# MCU.net
KiCad netlist of a schematic drawn in Altium Designer
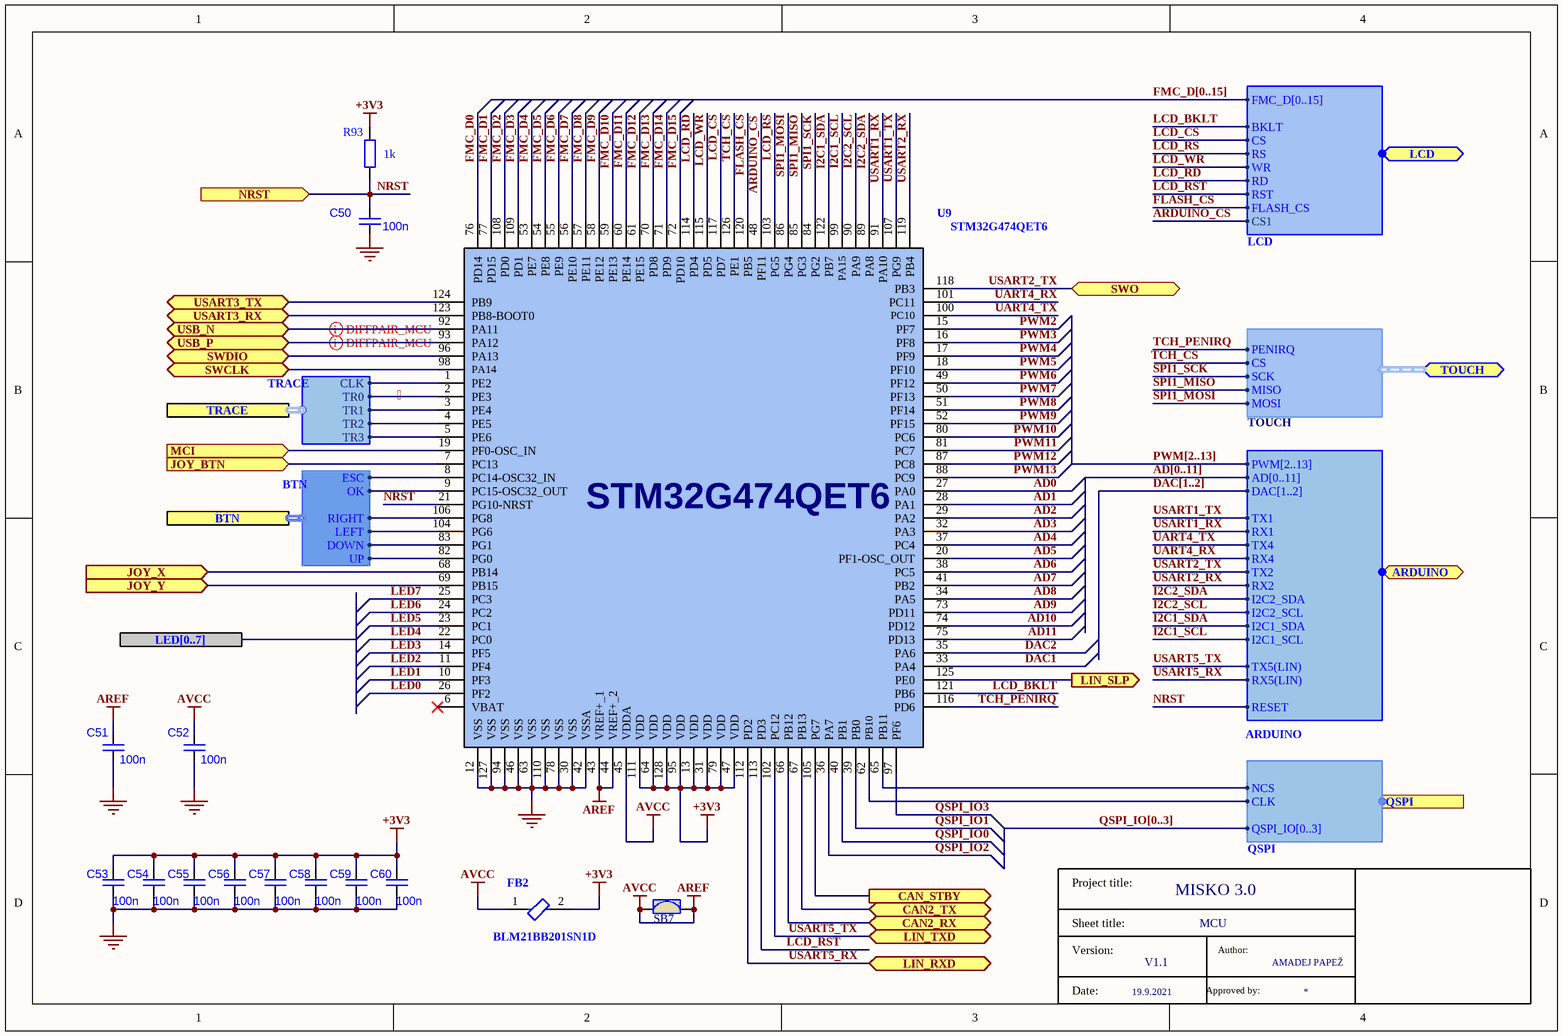
[diagram p0: MCU.SchDoc]

(export (version "E")
  (design (tool "Eeschema 10.0.6"))
  (components
    (comp (ref "C50")
      (value "100n")
      (footprint "C0603")
      (description "Capacitor")
      (libsource (lib "MISKO3_V6") (part "C"))
    )
    (comp (ref "C51")
      (value "100n")
      (footprint "C0603")
      (description "Capacitor")
      (libsource (lib "MISKO3_V6") (part "C"))
    )
    (comp (ref "C52")
      (value "100n")
      (footprint "C0603")
      (description "Capacitor")
      (libsource (lib "MISKO3_V6") (part "C"))
    )
    (comp (ref "C53")
      (value "100n")
      (footprint "C0603")
      (description "Capacitor")
      (libsource (lib "MISKO3_V6") (part "C"))
    )
    (comp (ref "C54")
      (value "100n")
      (footprint "C0603")
      (description "Capacitor")
      (libsource (lib "MISKO3_V6") (part "C"))
    )
    (comp (ref "C55")
      (value "100n")
      (footprint "C0603")
      (description "Capacitor")
      (libsource (lib "MISKO3_V6") (part "C"))
    )
    (comp (ref "C56")
      (value "100n")
      (footprint "C0603")
      (description "Capacitor")
      (libsource (lib "MISKO3_V6") (part "C"))
    )
    (comp (ref "C57")
      (value "100n")
      (footprint "C0603")
      (description "Capacitor")
      (libsource (lib "MISKO3_V6") (part "C"))
    )
    (comp (ref "C58")
      (value "100n")
      (footprint "C0603")
      (description "Capacitor")
      (libsource (lib "MISKO3_V6") (part "C"))
    )
    (comp (ref "C59")
      (value "100n")
      (footprint "C0603")
      (description "Capacitor")
      (libsource (lib "MISKO3_V6") (part "C"))
    )
    (comp (ref "C60")
      (value "100n")
      (footprint "C0603")
      (description "Capacitor")
      (libsource (lib "MISKO3_V6") (part "C"))
    )
    (comp (ref "FB2")
      (value "BLM21BB201SN1D")
      (footprint "BLM2102FB0805")
      (description "Chip Ferrite Bead, 0805, 200Ω @ 100MHz, 0.26Ω, 25%, 500mA")
      (fields (field (name "TOLERANCE") "25%"))
      (libsource (lib "MISKO3_V6") (part "BLM21BB201SN1D"))
    )
    (comp (ref "R93")
      (value "1k")
      (footprint "R1608_0603I_L")
      (description "R")
      (libsource (lib "MISKO3_V6") (part "R"))
    )
    (comp (ref "SB7")
      (value "SD_JUMP")
      (footprint "SOLDER_JUMPER")
      (libsource (lib "MISKO3_V6") (part "SD_JUMP"))
    )
    (comp (ref "T11") (value "~") (libsource (lib "MISKO3_V6") (part "Title block")))
    (comp (ref "U9")
      (value "STM32G474QET6")
      (footprint "QFP40P1600X1600X160-128N")
      (fields (field (name "MOUSER PART NUMBER") "511-STM32G474QET6"))
      (libsource (lib "MISKO3_V6") (part "STM32G474QET6"))
    )
  )
  (nets
    (net (code "7") (name "+3V3") (class "Default")
      (node (ref "C53") (pin "2") (pinfunction "2_2") (pintype "passive"))
      (node (ref "C54") (pin "2") (pinfunction "2_2") (pintype "passive"))
      (node (ref "C55") (pin "2") (pinfunction "2_2") (pintype "passive"))
      (node (ref "C56") (pin "2") (pinfunction "2_2") (pintype "passive"))
      (node (ref "C57") (pin "2") (pinfunction "2_2") (pintype "passive"))
      (node (ref "C58") (pin "2") (pinfunction "2_2") (pintype "passive"))
      (node (ref "C59") (pin "2") (pinfunction "2_2") (pintype "passive"))
      (node (ref "C60") (pin "2") (pinfunction "2_2") (pintype "passive"))
      (node (ref "FB2") (pin "2") (pinfunction "2_2") (pintype "passive"))
      (node (ref "R93") (pin "1") (pintype "passive"))
      (node (ref "U9") (pin "111") (pinfunction "VDD_111") (pintype "passive"))
      (node (ref "U9") (pin "128") (pinfunction "VDD_128") (pintype "passive"))
      (node (ref "U9") (pin "13") (pinfunction "VDD_13") (pintype "passive"))
      (node (ref "U9") (pin "31") (pinfunction "VDD_31") (pintype "passive"))
      (node (ref "U9") (pin "47") (pinfunction "VDD_47") (pintype "passive"))
      (node (ref "U9") (pin "64") (pinfunction "VDD_64") (pintype "passive"))
      (node (ref "U9") (pin "79") (pinfunction "VDD_79") (pintype "passive"))
      (node (ref "U9") (pin "95") (pinfunction "VDD_95") (pintype "passive"))
    )
    (net (code "9") (name "/AD0") (class "Default")
      (node (ref "U9") (pin "27") (pinfunction "PA0_27") (pintype "passive"))
    )
    (net (code "10") (name "/AD1") (class "Default")
      (node (ref "U9") (pin "28") (pinfunction "PA1_28") (pintype "passive"))
    )
    (net (code "11") (name "/AD2") (class "Default")
      (node (ref "U9") (pin "29") (pinfunction "PA2_29") (pintype "passive"))
    )
    (net (code "12") (name "/AD3") (class "Default")
      (node (ref "U9") (pin "32") (pinfunction "PA3_32") (pintype "passive"))
    )
    (net (code "13") (name "/AD4") (class "Default")
      (node (ref "U9") (pin "37") (pinfunction "PC4_37") (pintype "passive"))
    )
    (net (code "14") (name "/AD5") (class "Default")
      (node (ref "U9") (pin "20") (pinfunction "PF1-OSC_OUT_20") (pintype "passive"))
    )
    (net (code "15") (name "/AD6") (class "Default")
      (node (ref "U9") (pin "38") (pinfunction "PC5_38") (pintype "passive"))
    )
    (net (code "16") (name "/AD7") (class "Default")
      (node (ref "U9") (pin "41") (pinfunction "PB2_41") (pintype "passive"))
    )
    (net (code "17") (name "/AD8") (class "Default")
      (node (ref "U9") (pin "34") (pinfunction "PA5_34") (pintype "passive"))
    )
    (net (code "18") (name "/AD9") (class "Default")
      (node (ref "U9") (pin "73") (pinfunction "PD11_73") (pintype "passive"))
    )
    (net (code "19") (name "/AD10") (class "Default")
      (node (ref "U9") (pin "74") (pinfunction "PD12_74") (pintype "passive"))
    )
    (net (code "20") (name "/AD11") (class "Default")
      (node (ref "U9") (pin "75") (pinfunction "PD13_75") (pintype "passive"))
    )
    (net (code "22") (name "/ARDUINO_CS") (class "Default")
      (node (ref "U9") (pin "48") (pinfunction "PF11_48") (pintype "passive"))
    )
    (net (code "24") (name "/CAN2_RX") (class "Default")
      (node (ref "U9") (pin "66") (pinfunction "PB12_66") (pintype "passive"))
    )
    (net (code "25") (name "/CAN2_TX") (class "Default")
      (node (ref "U9") (pin "67") (pinfunction "PB13_67") (pintype "passive"))
    )
    (net (code "26") (name "/CAN_STBY") (class "Default")
      (node (ref "U9") (pin "105") (pinfunction "PG7_105") (pintype "passive"))
    )
    (net (code "27") (name "/DAC1") (class "Default")
      (node (ref "U9") (pin "33") (pinfunction "PA4_33") (pintype "passive"))
    )
    (net (code "28") (name "/DAC2") (class "Default")
      (node (ref "U9") (pin "35") (pinfunction "PA6_35") (pintype "passive"))
    )
    (net (code "29") (name "/DOWN") (class "Default")
      (node (ref "U9") (pin "83") (pinfunction "PG1_83") (pintype "passive"))
    )
    (net (code "30") (name "/ESC") (class "Default")
      (node (ref "U9") (pin "8") (pinfunction "PC14-OSC32_IN_8") (pintype "passive"))
    )
    (net (code "31") (name "/FLASH_CS") (class "Default")
      (node (ref "U9") (pin "120") (pinfunction "PB5_120") (pintype "passive"))
    )
    (net (code "32") (name "/FMC_D0") (class "Default")
      (node (ref "U9") (pin "76") (pinfunction "PD14_76") (pintype "passive"))
    )
    (net (code "33") (name "/FMC_D1") (class "Default")
      (node (ref "U9") (pin "77") (pinfunction "PD15_77") (pintype "passive"))
    )
    (net (code "34") (name "/FMC_D2") (class "Default")
      (node (ref "U9") (pin "108") (pinfunction "PD0_108") (pintype "passive"))
    )
    (net (code "35") (name "/FMC_D3") (class "Default")
      (node (ref "U9") (pin "109") (pinfunction "PD1_109") (pintype "passive"))
    )
    (net (code "36") (name "/FMC_D4") (class "Default")
      (node (ref "U9") (pin "53") (pinfunction "PE7_53") (pintype "passive"))
    )
    (net (code "37") (name "/FMC_D5") (class "Default")
      (node (ref "U9") (pin "54") (pinfunction "PE8_54") (pintype "passive"))
    )
    (net (code "38") (name "/FMC_D6") (class "Default")
      (node (ref "U9") (pin "55") (pinfunction "PE9_55") (pintype "passive"))
    )
    (net (code "39") (name "/FMC_D7") (class "Default")
      (node (ref "U9") (pin "56") (pinfunction "PE10_56") (pintype "passive"))
    )
    (net (code "40") (name "/FMC_D8") (class "Default")
      (node (ref "U9") (pin "57") (pinfunction "PE11_57") (pintype "passive"))
    )
    (net (code "41") (name "/FMC_D9") (class "Default")
      (node (ref "U9") (pin "58") (pinfunction "PE12_58") (pintype "passive"))
    )
    (net (code "42") (name "/FMC_D10") (class "Default")
      (node (ref "U9") (pin "59") (pinfunction "PE13_59") (pintype "passive"))
    )
    (net (code "43") (name "/FMC_D11") (class "Default")
      (node (ref "U9") (pin "60") (pinfunction "PE14_60") (pintype "passive"))
    )
    (net (code "44") (name "/FMC_D12") (class "Default")
      (node (ref "U9") (pin "61") (pinfunction "PE15_61") (pintype "passive"))
    )
    (net (code "45") (name "/FMC_D13") (class "Default")
      (node (ref "U9") (pin "70") (pinfunction "PD8_70") (pintype "passive"))
    )
    (net (code "46") (name "/FMC_D14") (class "Default")
      (node (ref "U9") (pin "71") (pinfunction "PD9_71") (pintype "passive"))
    )
    (net (code "47") (name "/FMC_D15") (class "Default")
      (node (ref "U9") (pin "72") (pinfunction "PD10_72") (pintype "passive"))
    )
    (net (code "48") (name "/I2C1_SCL") (class "Default")
      (node (ref "U9") (pin "99") (pinfunction "PA15_99") (pintype "passive"))
    )
    (net (code "49") (name "/I2C1_SDA") (class "Default")
      (node (ref "U9") (pin "122") (pinfunction "PB7_122") (pintype "passive"))
    )
    (net (code "50") (name "/I2C2_SCL") (class "Default")
      (node (ref "U9") (pin "90") (pinfunction "PA9_90") (pintype "passive"))
    )
    (net (code "51") (name "/I2C2_SDA") (class "Default")
      (node (ref "U9") (pin "89") (pinfunction "PA8_89") (pintype "passive"))
    )
    (net (code "52") (name "/JOY_BTN") (class "Default")
      (node (ref "U9") (pin "7") (pinfunction "PC13_7") (pintype "passive"))
    )
    (net (code "53") (name "/JOY_X") (class "Default")
      (node (ref "U9") (pin "68") (pinfunction "PB14_68") (pintype "passive"))
    )
    (net (code "54") (name "/JOY_Y") (class "Default")
      (node (ref "U9") (pin "69") (pinfunction "PB15_69") (pintype "passive"))
    )
    (net (code "55") (name "/LCD_BKLT") (class "Default")
      (node (ref "U9") (pin "121") (pinfunction "PB6_121") (pintype "passive"))
    )
    (net (code "56") (name "/LCD_CS") (class "Default")
      (node (ref "U9") (pin "117") (pinfunction "PD7_117") (pintype "passive"))
    )
    (net (code "57") (name "/LCD_RD") (class "Default")
      (node (ref "U9") (pin "114") (pinfunction "PD4_114") (pintype "passive"))
    )
    (net (code "58") (name "/LCD_RS") (class "Default")
      (node (ref "U9") (pin "103") (pinfunction "PG5_103") (pintype "passive"))
    )
    (net (code "59") (name "/LCD_RST") (class "Default")
      (node (ref "U9") (pin "113") (pinfunction "PD3_113") (pintype "passive"))
    )
    (net (code "60") (name "/LCD_WR") (class "Default")
      (node (ref "U9") (pin "115") (pinfunction "PD5_115") (pintype "passive"))
    )
    (net (code "62") (name "/LED0") (class "Default")
      (node (ref "U9") (pin "26") (pinfunction "PF2_26") (pintype "passive"))
    )
    (net (code "63") (name "/LED1") (class "Default")
      (node (ref "U9") (pin "10") (pinfunction "PF3_10") (pintype "passive"))
    )
    (net (code "64") (name "/LED2") (class "Default")
      (node (ref "U9") (pin "11") (pinfunction "PF4_11") (pintype "passive"))
    )
    (net (code "65") (name "/LED3") (class "Default")
      (node (ref "U9") (pin "14") (pinfunction "PF5_14") (pintype "passive"))
    )
    (net (code "66") (name "/LED4") (class "Default")
      (node (ref "U9") (pin "22") (pinfunction "PC0_22") (pintype "passive"))
    )
    (net (code "67") (name "/LED5") (class "Default")
      (node (ref "U9") (pin "23") (pinfunction "PC1_23") (pintype "passive"))
    )
    (net (code "68") (name "/LED6") (class "Default")
      (node (ref "U9") (pin "24") (pinfunction "PC2_24") (pintype "passive"))
    )
    (net (code "69") (name "/LED7") (class "Default")
      (node (ref "U9") (pin "25") (pinfunction "PC3_25") (pintype "passive"))
    )
    (net (code "71") (name "/LEFT") (class "Default")
      (node (ref "U9") (pin "104") (pinfunction "PG6_104") (pintype "passive"))
    )
    (net (code "72") (name "/LIN_SLP") (class "Default")
      (node (ref "U9") (pin "125") (pinfunction "PE0_125") (pintype "passive"))
    )
    (net (code "73") (name "/MCI") (class "Default")
      (node (ref "U9") (pin "19") (pinfunction "PF0-OSC_IN_19") (pintype "passive"))
    )
    (net (code "74") (name "/NCS") (class "Default")
      (node (ref "U9") (pin "65") (pinfunction "PB11_65") (pintype "passive"))
    )
    (net (code "75") (name "/NRST") (class "Default")
      (node (ref "C50") (pin "2") (pinfunction "2_2") (pintype "passive"))
      (node (ref "R93") (pin "2") (pintype "passive"))
      (node (ref "U9") (pin "21") (pinfunction "PG10-NRST_21") (pintype "passive"))
    )
    (net (code "76") (name "/OK") (class "Default")
      (node (ref "U9") (pin "9") (pinfunction "PC15-OSC32_OUT_9") (pintype "passive"))
    )
    (net (code "77") (name "/PWM2") (class "Default")
      (node (ref "U9") (pin "15") (pinfunction "PF7_15") (pintype "passive"))
    )
    (net (code "78") (name "/PWM3") (class "Default")
      (node (ref "U9") (pin "16") (pinfunction "PF8_16") (pintype "passive"))
    )
    (net (code "79") (name "/PWM4") (class "Default")
      (node (ref "U9") (pin "17") (pinfunction "PF9_17") (pintype "passive"))
    )
    (net (code "80") (name "/PWM5") (class "Default")
      (node (ref "U9") (pin "18") (pinfunction "PF10_18") (pintype "passive"))
    )
    (net (code "81") (name "/PWM6") (class "Default")
      (node (ref "U9") (pin "49") (pinfunction "PF12_49") (pintype "passive"))
    )
    (net (code "82") (name "/PWM7") (class "Default")
      (node (ref "U9") (pin "50") (pinfunction "PF13_50") (pintype "passive"))
    )
    (net (code "83") (name "/PWM8") (class "Default")
      (node (ref "U9") (pin "51") (pinfunction "PF14_51") (pintype "passive"))
    )
    (net (code "84") (name "/PWM9") (class "Default")
      (node (ref "U9") (pin "52") (pinfunction "PF15_52") (pintype "passive"))
    )
    (net (code "85") (name "/PWM10") (class "Default")
      (node (ref "U9") (pin "80") (pinfunction "PC6_80") (pintype "passive"))
    )
    (net (code "86") (name "/PWM11") (class "Default")
      (node (ref "U9") (pin "81") (pinfunction "PC7_81") (pintype "passive"))
    )
    (net (code "87") (name "/PWM12") (class "Default")
      (node (ref "U9") (pin "87") (pinfunction "PC8_87") (pintype "passive"))
    )
    (net (code "88") (name "/PWM13") (class "Default")
      (node (ref "U9") (pin "88") (pinfunction "PC9_88") (pintype "passive"))
    )
    (net (code "90") (name "/QSPI_IO0") (class "Default")
      (node (ref "U9") (pin "40") (pinfunction "PB1_40") (pintype "passive"))
    )
    (net (code "91") (name "/QSPI_IO1") (class "Default")
      (node (ref "U9") (pin "39") (pinfunction "PB0_39") (pintype "passive"))
    )
    (net (code "92") (name "/QSPI_IO2") (class "Default")
      (node (ref "U9") (pin "36") (pinfunction "PA7_36") (pintype "passive"))
    )
    (net (code "93") (name "/QSPI_IO3") (class "Default")
      (node (ref "U9") (pin "97") (pinfunction "PF6_97") (pintype "passive"))
    )
    (net (code "95") (name "/RIGHT") (class "Default")
      (node (ref "U9") (pin "106") (pinfunction "PG8_106") (pintype "passive"))
    )
    (net (code "96") (name "/SPI1_MISO") (class "Default")
      (node (ref "U9") (pin "85") (pinfunction "PG3_85") (pintype "passive"))
    )
    (net (code "97") (name "/SPI1_MOSI") (class "Default")
      (node (ref "U9") (pin "86") (pinfunction "PG4_86") (pintype "passive"))
    )
    (net (code "98") (name "/SPI1_SCK") (class "Default")
      (node (ref "U9") (pin "84") (pinfunction "PG2_84") (pintype "passive"))
    )
    (net (code "99") (name "/SWCLK") (class "Default")
      (node (ref "U9") (pin "98") (pinfunction "PA14_98") (pintype "passive"))
    )
    (net (code "100") (name "/SWDIO") (class "Default")
      (node (ref "U9") (pin "96") (pinfunction "PA13_96") (pintype "passive"))
    )
    (net (code "101") (name "/TCH_CS") (class "Default")
      (node (ref "U9") (pin "126") (pinfunction "PE1_126") (pintype "passive"))
    )
    (net (code "102") (name "/TCH_PENIRQ") (class "Default")
      (node (ref "U9") (pin "116") (pinfunction "PD6_116") (pintype "passive"))
    )
    (net (code "103") (name "/TR0") (class "Default")
      (node (ref "U9") (pin "2") (pinfunction "PE3_2") (pintype "passive"))
    )
    (net (code "104") (name "/TR1") (class "Default")
      (node (ref "U9") (pin "3") (pinfunction "PE4_3") (pintype "passive"))
    )
    (net (code "105") (name "/TR2") (class "Default")
      (node (ref "U9") (pin "4") (pinfunction "PE5_4") (pintype "passive"))
    )
    (net (code "106") (name "/TR3") (class "Default")
      (node (ref "U9") (pin "5") (pinfunction "PE6_5") (pintype "passive"))
    )
    (net (code "107") (name "/UART4_RX") (class "Default")
      (node (ref "U9") (pin "101") (pinfunction "PC11_101") (pintype "passive"))
    )
    (net (code "108") (name "/UART4_TX") (class "Default")
      (node (ref "U9") (pin "100") (pinfunction "PC10_100") (pintype "passive"))
    )
    (net (code "109") (name "/UP") (class "Default")
      (node (ref "U9") (pin "82") (pinfunction "PG0_82") (pintype "passive"))
    )
    (net (code "110") (name "/USART1_RX") (class "Default")
      (node (ref "U9") (pin "91") (pinfunction "PA10_91") (pintype "passive"))
    )
    (net (code "111") (name "/USART1_TX") (class "Default")
      (node (ref "U9") (pin "107") (pinfunction "PG9_107") (pintype "passive"))
    )
    (net (code "112") (name "/USART2_RX") (class "Default")
      (node (ref "U9") (pin "119") (pinfunction "PB4_119") (pintype "passive"))
    )
    (net (code "113") (name "/USART2_TX") (class "Default")
      (node (ref "U9") (pin "118") (pinfunction "PB3_118") (pintype "passive"))
    )
    (net (code "114") (name "/USART3_RX") (class "Default")
      (node (ref "U9") (pin "123") (pinfunction "PB8-BOOT0_123") (pintype "passive"))
    )
    (net (code "115") (name "/USART3_TX") (class "Default")
      (node (ref "U9") (pin "124") (pinfunction "PB9_124") (pintype "passive"))
    )
    (net (code "116") (name "/USART5_RX") (class "Default")
      (node (ref "U9") (pin "112") (pinfunction "PD2_112") (pintype "passive"))
    )
    (net (code "117") (name "/USART5_TX") (class "Default")
      (node (ref "U9") (pin "102") (pinfunction "PC12_102") (pintype "passive"))
    )
    (net (code "118") (name "/USB_N") (class "Default")
      (node (ref "U9") (pin "92") (pinfunction "PA11_92") (pintype "passive"))
    )
    (net (code "119") (name "/USB_P") (class "Default")
      (node (ref "U9") (pin "93") (pinfunction "PA12_93") (pintype "passive"))
    )
    (net (code "126") (name "AREF") (class "Default")
      (node (ref "C51") (pin "2") (pinfunction "2_2") (pintype "passive"))
      (node (ref "C52") (pin "2") (pinfunction "2_2") (pintype "passive"))
      (node (ref "FB2") (pin "1") (pinfunction "1_1") (pintype "passive"))
      (node (ref "SB7") (pin "1") (pinfunction "37_1") (pintype "passive"))
      (node (ref "SB7") (pin "2") (pinfunction "38_2") (pintype "passive"))
      (node (ref "U9") (pin "43") (pinfunction "VREF+_1_43") (pintype "passive"))
      (node (ref "U9") (pin "44") (pinfunction "VREF+_2_44") (pintype "passive"))
      (node (ref "U9") (pin "45") (pinfunction "VDDA_45") (pintype "passive"))
    )
    (net (code "127") (name "GND") (class "Default")
      (node (ref "C50") (pin "1") (pinfunction "1_1") (pintype "passive"))
      (node (ref "C51") (pin "1") (pinfunction "1_1") (pintype "passive"))
      (node (ref "C52") (pin "1") (pinfunction "1_1") (pintype "passive"))
      (node (ref "C53") (pin "1") (pinfunction "1_1") (pintype "passive"))
      (node (ref "C54") (pin "1") (pinfunction "1_1") (pintype "passive"))
      (node (ref "C55") (pin "1") (pinfunction "1_1") (pintype "passive"))
      (node (ref "C56") (pin "1") (pinfunction "1_1") (pintype "passive"))
      (node (ref "C57") (pin "1") (pinfunction "1_1") (pintype "passive"))
      (node (ref "C58") (pin "1") (pinfunction "1_1") (pintype "passive"))
      (node (ref "C59") (pin "1") (pinfunction "1_1") (pintype "passive"))
      (node (ref "C60") (pin "1") (pinfunction "1_1") (pintype "passive"))
      (node (ref "U9") (pin "110") (pinfunction "VSS_110") (pintype "passive"))
      (node (ref "U9") (pin "12") (pinfunction "VSS_12") (pintype "passive"))
      (node (ref "U9") (pin "127") (pinfunction "VSS_127") (pintype "passive"))
      (node (ref "U9") (pin "30") (pinfunction "VSS_30") (pintype "passive"))
      (node (ref "U9") (pin "42") (pinfunction "VSSA_42") (pintype "passive"))
      (node (ref "U9") (pin "46") (pinfunction "VSS_46") (pintype "passive"))
      (node (ref "U9") (pin "63") (pinfunction "VSS_63") (pintype "passive"))
      (node (ref "U9") (pin "78") (pinfunction "VSS_78") (pintype "passive"))
      (node (ref "U9") (pin "94") (pinfunction "VSS_94") (pintype "passive"))
    )
    (net (code "128") (name "unconnected-(U9-PB10-Pad62)") (class "Default")
      (node (ref "U9") (pin "62") (pinfunction "PB10_62") (pintype "passive"))
    )
    (net (code "129") (name "unconnected-(U9-PE2-Pad1)") (class "Default")
      (node (ref "U9") (pin "1") (pinfunction "PE2_1") (pintype "passive"))
    )
    (net (code "130") (name "unconnected-(U9-VBAT-Pad6)") (class "Default")
      (node (ref "U9") (pin "6") (pinfunction "VBAT_6") (pintype "passive+no_connect"))
    )
  )
)
